# GPS.net
KiCad netlist of a schematic drawn in Altium Designer
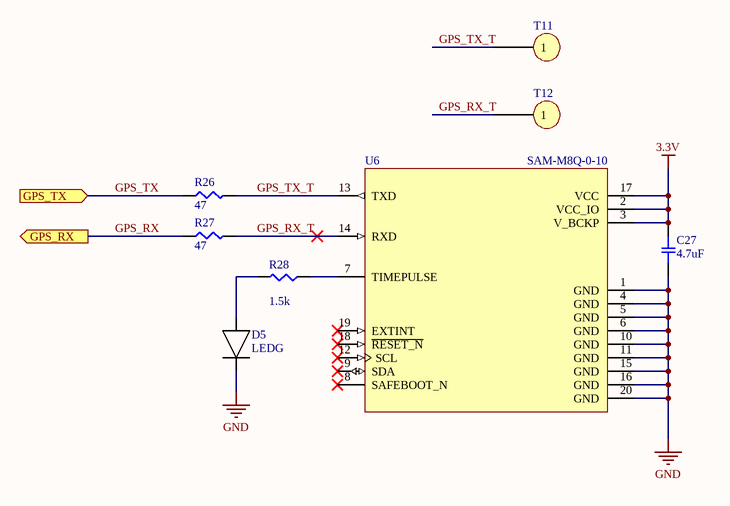
[diagram p0: GPS.SchDoc]

(export (version "E")
  (design (tool "Eeschema 10.0.6"))
  (components
    (comp (ref "C27")
      (value "4.7uF")
      (footprint "0603-CAP")
      (fields (field (name "Comment") "0603C 4U7F"))
      (libsource (lib "passive components") (part "0603C 4U7F"))
    )
    (comp (ref "D5")
      (value "LEDG")
      (footprint "0603-LED")
      (libsource (lib "passive components") (part "0603 LEDG"))
    )
    (comp (ref "R26")
      (value "47")
      (footprint "0603-RES")
      (fields (field (name "Comment") "0603R 47R"))
      (libsource (lib "passive components") (part "0603R 47R"))
    )
    (comp (ref "R27")
      (value "47")
      (footprint "0603-RES")
      (fields (field (name "Comment") "0603R 47R"))
      (libsource (lib "passive components") (part "0603R 47R"))
    )
    (comp (ref "R28")
      (value "1.5k")
      (footprint "0603-RES")
      (fields (field (name "Comment") "0603R 1K5R"))
      (libsource (lib "passive components") (part "0603R 1K5R"))
    )
    (comp (ref "T11") (value "*") (footprint "1_PIN_test") (libsource (lib "*") (part "1pin_header")))
    (comp (ref "T12") (value "*") (footprint "1_PIN_test") (libsource (lib "*") (part "1pin_header")))
    (comp (ref "U6")
      (value "SAM-M8Q-0-10")
      (footprint "SAMM8Q010")
      (description "CAM-M8 RF Receiver BeiDou, GLONASS, GNSS, GPS 1.575GHz -167dBm On-Board, Chip Module")
      (fields (field (name "MF") "U-Blox America") (field (name "DIGI-KEY_PART_NUMBER") "672-1054-1-ND"))
      (libsource (lib "GPS") (part "SAM-M8Q-0-10"))
    )
  )
  (nets
    (net (code "1") (name "/GPS_RX") (class "Default")
      (node (ref "R27") (pin "1") (pinfunction "1_1") (pintype "passive"))
    )
    (net (code "2") (name "/GPS_RX_T") (class "Default")
      (node (ref "R27") (pin "2") (pinfunction "2_2") (pintype "passive"))
      (node (ref "T12") (pin "1") (pinfunction "1_1") (pintype "passive"))
      (node (ref "U6") (pin "14") (pinfunction "RXD_14") (pintype "input"))
    )
    (net (code "3") (name "/GPS_TX") (class "Default")
      (node (ref "R26") (pin "1") (pinfunction "1_1") (pintype "passive"))
    )
    (net (code "4") (name "/GPS_TX_T") (class "Default")
      (node (ref "R26") (pin "2") (pinfunction "2_2") (pintype "passive"))
      (node (ref "T11") (pin "1") (pinfunction "1_1") (pintype "passive"))
      (node (ref "U6") (pin "13") (pinfunction "TXD_13") (pintype "output"))
    )
    (net (code "5") (name "3.3V") (class "Default")
      (node (ref "C27") (pin "1") (pinfunction "1_1") (pintype "passive"))
      (node (ref "U6") (pin "17") (pinfunction "VCC_17") (pintype "power_in"))
      (node (ref "U6") (pin "2") (pinfunction "VCC_IO_2") (pintype "power_in"))
      (node (ref "U6") (pin "3") (pinfunction "V_BCKP_3") (pintype "power_in"))
    )
    (net (code "6") (name "GND") (class "Default")
      (node (ref "C27") (pin "2") (pinfunction "2_2") (pintype "passive"))
      (node (ref "D5") (pin "2") (pinfunction "2_2") (pintype "passive"))
      (node (ref "U6") (pin "1") (pinfunction "GND_1") (pintype "power_in"))
      (node (ref "U6") (pin "10") (pinfunction "GND_10") (pintype "power_in"))
      (node (ref "U6") (pin "11") (pinfunction "GND_11") (pintype "power_in"))
      (node (ref "U6") (pin "15") (pinfunction "GND_15") (pintype "power_in"))
      (node (ref "U6") (pin "16") (pinfunction "GND_16") (pintype "power_in"))
      (node (ref "U6") (pin "20") (pinfunction "GND_20") (pintype "power_in"))
      (node (ref "U6") (pin "4") (pinfunction "GND_4") (pintype "power_in"))
      (node (ref "U6") (pin "5") (pinfunction "GND_5") (pintype "power_in"))
      (node (ref "U6") (pin "6") (pinfunction "GND_6") (pintype "power_in"))
    )
    (net (code "7") (name "Net-(D5-Pad1)") (class "Default")
      (node (ref "D5") (pin "1") (pinfunction "1_1") (pintype "passive"))
      (node (ref "R28") (pin "2") (pinfunction "2_2") (pintype "passive"))
    )
    (net (code "8") (name "Net-(U6-TIMEPULSE)") (class "Default")
      (node (ref "R28") (pin "1") (pinfunction "1_1") (pintype "passive"))
      (node (ref "U6") (pin "7") (pinfunction "TIMEPULSE_7") (pintype "passive"))
    )
    (net (code "9") (name "unconnected-(U6-EXTINT-Pad19)") (class "Default")
      (node (ref "U6") (pin "19") (pinfunction "EXTINT_19") (pintype "input+no_connect"))
    )
    (net (code "10") (name "unconnected-(U6-SAFEBOOT_N-Pad8)") (class "Default")
      (node (ref "U6") (pin "8") (pinfunction "SAFEBOOT_N_8") (pintype "passive+no_connect"))
    )
    (net (code "11") (name "unconnected-(U6-SCL-Pad12)") (class "Default")
      (node (ref "U6") (pin "12") (pinfunction "SCL_12") (pintype "input+no_connect"))
    )
    (net (code "12") (name "unconnected-(U6-SDA-Pad9)") (class "Default")
      (node (ref "U6") (pin "9") (pinfunction "SDA_9") (pintype "bidirectional+no_connect"))
    )
    (net (code "13") (name "unconnected-(U6-~{RESET_N}-Pad18)") (class "Default")
      (node (ref "U6") (pin "18") (pinfunction "~{RESET_N}_18") (pintype "input+no_connect"))
    )
  )
)
